# MR_UartConnector.net
KiCad netlist of a schematic drawn in Altium Designer
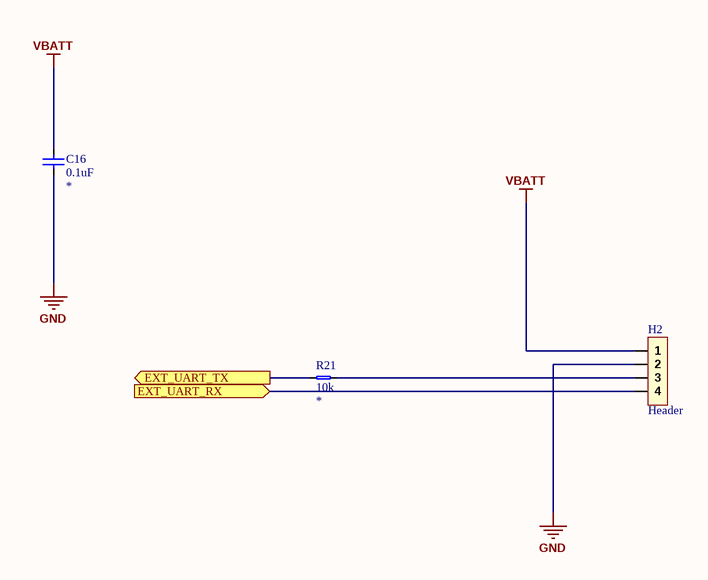
[diagram p0: MR_UartConnector.SchDoc]

(export (version "E")
  (design (tool "Eeschema 10.0.6"))
  (components
    (comp (ref "C16")
      (value "0.1uF")
      (footprint "0603_CAP_LD")
      (description "Ceramic Capacitor")
      (fields (field (name "PACKAGE") "*") (field (name "Comment") "CerCap"))
      (libsource (lib "MiniRobot") (part "CerCap"))
    )
    (comp (ref "H2")
      (value "Header")
      (footprint "HE14 1x4 Straight")
      (description "Header 4x1 PIns")
      (libsource (lib "MiniRobot") (part "Header_4x1"))
    )
    (comp (ref "R21")
      (value "10k")
      (footprint "0603_RES_LD")
      (description "Resistor")
      (fields (field (name "PACKAGE") "*"))
      (libsource (lib "MiniRobot") (part "Resistor"))
    )
  )
  (nets
    (net (code "1") (name "/EXT_UART_RX") (class "Default")
      (node (ref "H2") (pin "4") (pinfunction "4_4") (pintype "passive"))
    )
    (net (code "2") (name "/EXT_UART_TX") (class "Default")
      (node (ref "R21") (pin "1") (pinfunction "1_1") (pintype "passive"))
    )
    (net (code "3") (name "GND") (class "Default")
      (node (ref "C16") (pin "1") (pinfunction "1_1") (pintype "passive"))
      (node (ref "H2") (pin "2") (pinfunction "2_2") (pintype "passive"))
    )
    (net (code "4") (name "Net-(H2-Pad3)") (class "Default")
      (node (ref "H2") (pin "3") (pinfunction "3_3") (pintype "passive"))
      (node (ref "R21") (pin "2") (pinfunction "2_2") (pintype "passive"))
    )
    (net (code "5") (name "VBATT") (class "Default")
      (node (ref "C16") (pin "2") (pinfunction "2_2") (pintype "passive"))
      (node (ref "H2") (pin "1") (pinfunction "1_1") (pintype "passive"))
    )
  )
)
